# ResistorNetwork_forTest.net
KiCad netlist of a schematic drawn in Altium Designer
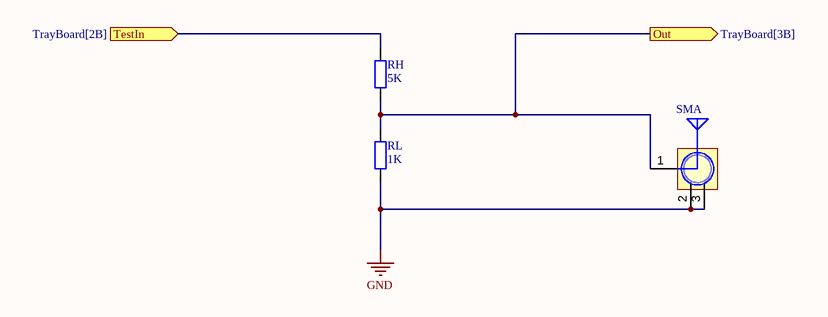
[diagram p0: ResistorNetwork_forTest.SchDoc]

(export (version "E")
  (design (tool "Eeschema 10.0.6"))
  (components
    (comp (ref "RH")
      (value "5K")
      (footprint "R 0402_L")
      (description "贴片电阻 0.1%\r\nC3202451")
      (fields (field (name "版权归属") "来自淘宝 ID：黄晶宝石"))
      (libsource (lib "0.1 - 电阻-电容-电感") (part "R"))
    )
    (comp (ref "RL")
      (value "1K")
      (footprint "R 0402_L")
      (description "贴片电阻 0.1%")
      (fields (field (name "版权归属") "来自淘宝 ID：黄晶宝石"))
      (libsource (lib "0.1 - 电阻-电容-电感") (part "R"))
    )
    (comp (ref "SMA")
      (value "SMA RF 立式")
      (footprint "SMA-KE-LI")
      (fields (field (name "版权归属") "封装库来自淘宝 ID：黄晶宝石"))
      (libsource (lib "1.8 - WiFi天线-SMA射频座") (part "SMA"))
    )
  )
  (nets
    (net (code "1") (name "/Out") (class "Default")
      (node (ref "RH") (pin "1") (pinfunction "1_1") (pintype "passive"))
      (node (ref "RL") (pin "2") (pinfunction "2_2") (pintype "passive"))
      (node (ref "SMA") (pin "1") (pinfunction "ANT_1") (pintype "passive"))
    )
    (net (code "2") (name "/TestIn") (class "Default")
      (node (ref "RH") (pin "2") (pinfunction "2_2") (pintype "passive"))
    )
    (net (code "3") (name "GND") (class "Default")
      (node (ref "RL") (pin "1") (pinfunction "1_1") (pintype "passive"))
      (node (ref "SMA") (pin "2") (pinfunction "GND_2") (pintype "passive"))
      (node (ref "SMA") (pin "3") (pinfunction "GND_3") (pintype "passive"))
    )
  )
)
